# mp3-trigger.net
KiCad netlist of a schematic drawn in EAGLE
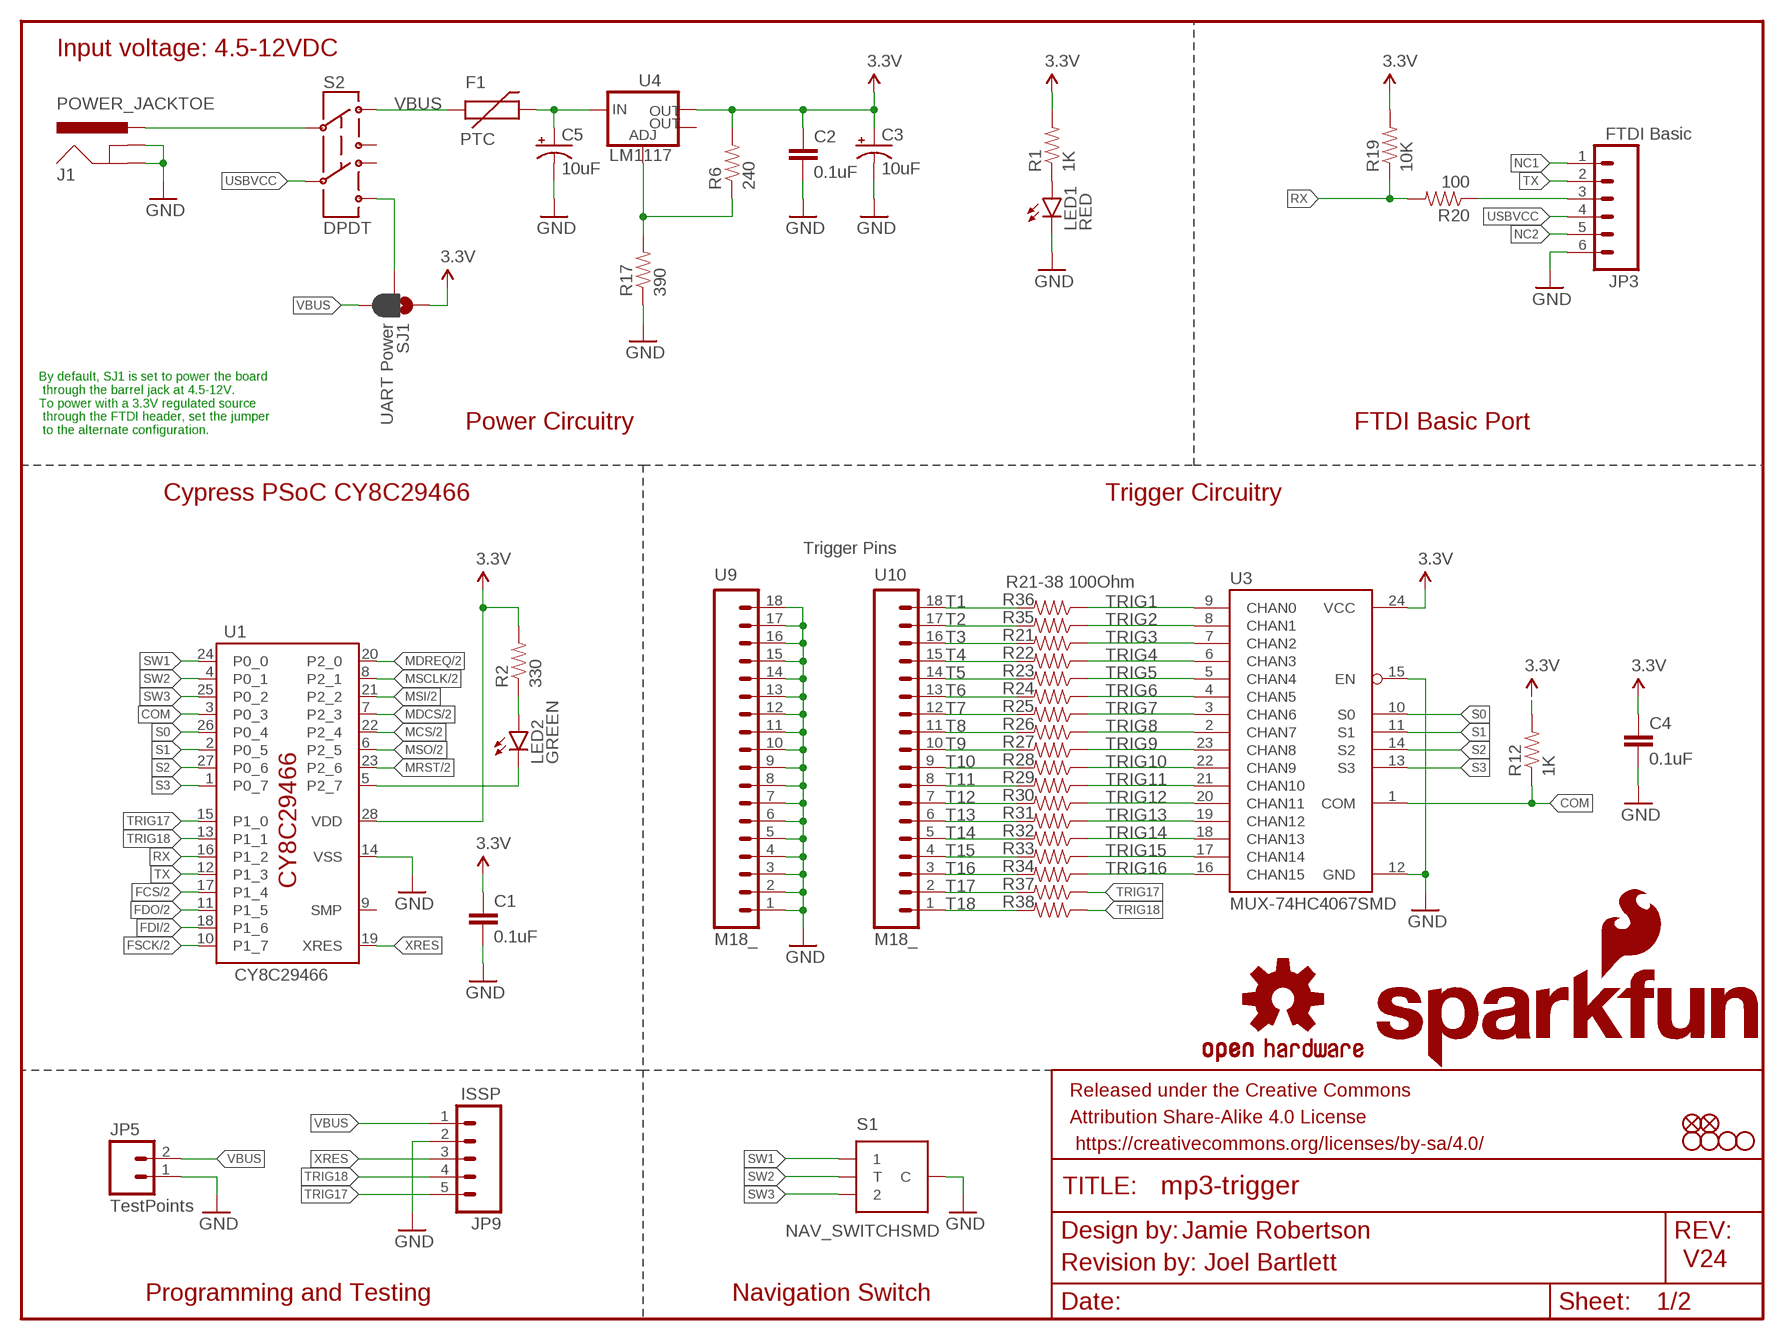
[diagram p0: schematic, sheet 1]
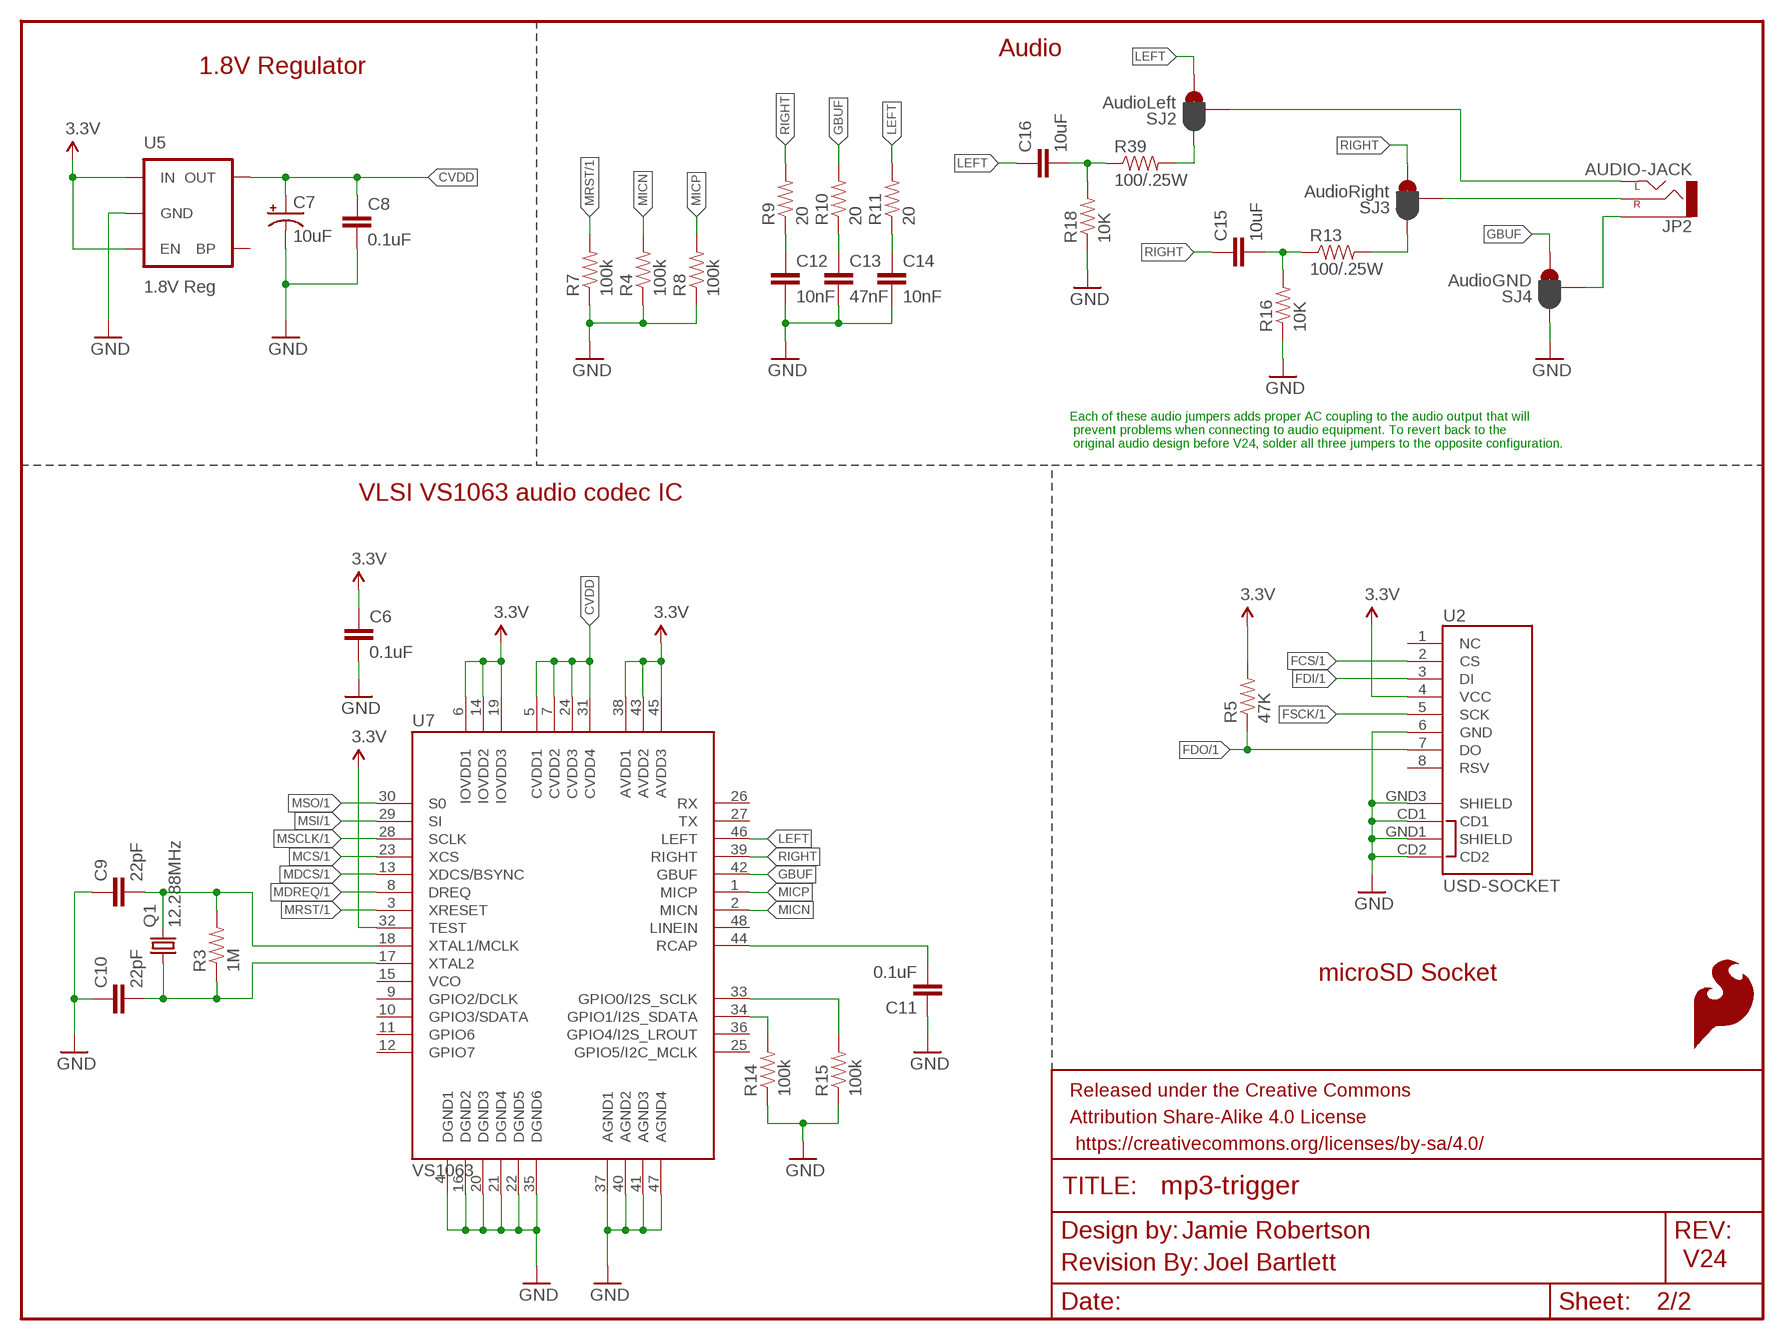
[diagram p1: schematic, sheet 2]

(export (version "E")
  (design (tool "Eeschema 10.0.6"))
  (components
    (comp (ref "C1")
      (value "0.1uF")
      (footprint "eagle-import:0603-CAP")
      (libsource (lib "eagle-import") (part "0.1UF-25V(+80/-20%)(0603)"))
    )
    (comp (ref "C2")
      (value "0.1uF")
      (footprint "eagle-import:0603-CAP")
      (libsource (lib "eagle-import") (part "0.1UF-25V(+80/-20%)(0603)"))
    )
    (comp (ref "C3")
      (value "10uF")
      (footprint "eagle-import:EIA3216")
      (libsource (lib "eagle-import") (part "10UF-16V-10%(TANT)"))
    )
    (comp (ref "C4")
      (value "0.1uF")
      (footprint "eagle-import:0603-CAP")
      (libsource (lib "eagle-import") (part "0.1UF-25V(+80/-20%)(0603)"))
    )
    (comp (ref "C5")
      (value "10uF")
      (footprint "eagle-import:EIA3216")
      (libsource (lib "eagle-import") (part "10UF-16V-10%(TANT)"))
    )
    (comp (ref "F1")
      (value "PTC")
      (footprint "eagle-import:PTC-1206")
      (libsource (lib "eagle-import") (part "PTCTHERMISTOR1206"))
    )
    (comp (ref "FRAME3")
      (value "FRAME-LETTER")
      (footprint "eagle-import:CREATIVE_COMMONS")
      (libsource (lib "eagle-import") (part "FRAME-LETTER"))
    )
    (comp (ref "J1")
      (value "POWER_JACKTOE")
      (footprint "eagle-import:POWER_JACK_SMD_OVERPASTE_TOE")
      (libsource (lib "eagle-import") (part "POWER_JACKTOE"))
    )
    (comp (ref "JP3")
      (value "FTDI Basic")
      (footprint "eagle-import:1X06")
      (libsource (lib "eagle-import") (part "M06SIP"))
    )
    (comp (ref "JP5")
      (value "TestPoints")
      (footprint "eagle-import:1X02")
      (libsource (lib "eagle-import") (part "M02PTH"))
    )
    (comp (ref "JP6")
      (value "FIDUCIAL1X2")
      (footprint "eagle-import:FIDUCIAL-1X2")
      (libsource (lib "eagle-import") (part "FIDUCIAL1X2"))
    )
    (comp (ref "JP7")
      (value "FIDUCIAL1X2")
      (footprint "eagle-import:FIDUCIAL-1X2")
      (libsource (lib "eagle-import") (part "FIDUCIAL1X2"))
    )
    (comp (ref "JP9")
      (value "ISSP")
      (footprint "eagle-import:1X05")
      (libsource (lib "eagle-import") (part "M05PTH"))
    )
    (comp (ref "LED1")
      (value "RED")
      (footprint "eagle-import:LED-1206")
      (libsource (lib "eagle-import") (part "LED-RED1206"))
    )
    (comp (ref "LED2")
      (value "GREEN")
      (footprint "eagle-import:LED-1206")
      (libsource (lib "eagle-import") (part "LED-GREEN1206"))
    )
    (comp (ref "LOGO3")
      (value "OSHW-LOGOM")
      (footprint "eagle-import:OSHW-LOGO-M")
      (libsource (lib "eagle-import") (part "OSHW-LOGOM"))
    )
    (comp (ref "R1")
      (value "1K")
      (footprint "eagle-import:0603-RES")
      (libsource (lib "eagle-import") (part "1KOHM-1/10W-1%(0603)"))
    )
    (comp (ref "R2")
      (value "330")
      (footprint "eagle-import:0603-RES")
      (libsource (lib "eagle-import") (part "330OHM1/10W1%(0603)"))
    )
    (comp (ref "R6")
      (value "240")
      (footprint "eagle-import:0603-RES")
      (libsource (lib "eagle-import") (part "240OHM1/10W1%(0603)"))
    )
    (comp (ref "R12")
      (value "1K")
      (footprint "eagle-import:0603-RES")
      (libsource (lib "eagle-import") (part "1KOHM-1/10W-1%(0603)"))
    )
    (comp (ref "R17")
      (value "390")
      (footprint "eagle-import:0603-RES")
      (libsource (lib "eagle-import") (part "390OHM1/10W1%(0603)"))
    )
    (comp (ref "R19")
      (value "10K")
      (footprint "eagle-import:0603-RES")
      (libsource (lib "eagle-import") (part "10KOHM-1/10W-1%(0603)0603"))
    )
    (comp (ref "R20")
      (value "100")
      (footprint "eagle-import:0603-RES")
      (libsource (lib "eagle-import") (part "100OHM-1/10W-1%(0603)"))
    )
    (comp (ref "R21")
      (value "100")
      (footprint "eagle-import:0603-RES")
      (libsource (lib "eagle-import") (part "100OHM-1/10W-1%(0603)"))
    )
    (comp (ref "R22")
      (value "100")
      (footprint "eagle-import:0603-RES")
      (libsource (lib "eagle-import") (part "100OHM-1/10W-1%(0603)"))
    )
    (comp (ref "R23")
      (value "100")
      (footprint "eagle-import:0603-RES")
      (libsource (lib "eagle-import") (part "100OHM-1/10W-1%(0603)"))
    )
    (comp (ref "R24")
      (value "100")
      (footprint "eagle-import:0603-RES")
      (libsource (lib "eagle-import") (part "100OHM-1/10W-1%(0603)"))
    )
    (comp (ref "R25")
      (value "100")
      (footprint "eagle-import:0603-RES")
      (libsource (lib "eagle-import") (part "100OHM-1/10W-1%(0603)"))
    )
    (comp (ref "R26")
      (value "100")
      (footprint "eagle-import:0603-RES")
      (libsource (lib "eagle-import") (part "100OHM-1/10W-1%(0603)"))
    )
    (comp (ref "R27")
      (value "100")
      (footprint "eagle-import:0603-RES")
      (libsource (lib "eagle-import") (part "100OHM-1/10W-1%(0603)"))
    )
    (comp (ref "R28")
      (value "100")
      (footprint "eagle-import:0603-RES")
      (libsource (lib "eagle-import") (part "100OHM-1/10W-1%(0603)"))
    )
    (comp (ref "R29")
      (value "100")
      (footprint "eagle-import:0603-RES")
      (libsource (lib "eagle-import") (part "100OHM-1/10W-1%(0603)"))
    )
    (comp (ref "R30")
      (value "100")
      (footprint "eagle-import:0603-RES")
      (libsource (lib "eagle-import") (part "100OHM-1/10W-1%(0603)"))
    )
    (comp (ref "R31")
      (value "100")
      (footprint "eagle-import:0603-RES")
      (libsource (lib "eagle-import") (part "100OHM-1/10W-1%(0603)"))
    )
    (comp (ref "R32")
      (value "100")
      (footprint "eagle-import:0603-RES")
      (libsource (lib "eagle-import") (part "100OHM-1/10W-1%(0603)"))
    )
    (comp (ref "R33")
      (value "100")
      (footprint "eagle-import:0603-RES")
      (libsource (lib "eagle-import") (part "100OHM-1/10W-1%(0603)"))
    )
    (comp (ref "R34")
      (value "100")
      (footprint "eagle-import:0603-RES")
      (libsource (lib "eagle-import") (part "100OHM-1/10W-1%(0603)"))
    )
    (comp (ref "R35")
      (value "100")
      (footprint "eagle-import:0603-RES")
      (libsource (lib "eagle-import") (part "100OHM-1/10W-1%(0603)"))
    )
    (comp (ref "R36")
      (value "100")
      (footprint "eagle-import:0603-RES")
      (libsource (lib "eagle-import") (part "100OHM-1/10W-1%(0603)"))
    )
    (comp (ref "R37")
      (value "100")
      (footprint "eagle-import:0603-RES")
      (libsource (lib "eagle-import") (part "100OHM-1/10W-1%(0603)"))
    )
    (comp (ref "R38")
      (value "100")
      (footprint "eagle-import:0603-RES")
      (libsource (lib "eagle-import") (part "100OHM-1/10W-1%(0603)"))
    )
    (comp (ref "S1")
      (value "NAV_SWITCHSMD")
      (footprint "eagle-import:NAV_SWITCH")
      (libsource (lib "eagle-import") (part "NAV_SWITCHSMD"))
    )
    (comp (ref "S2")
      (value "DPDT")
      (footprint "eagle-import:AYZ0202")
      (libsource (lib "eagle-import") (part "SWITCH-DPDTAYZ0202"))
    )
    (comp (ref "SJ1")
      (value "UART Power")
      (footprint "eagle-import:PAD-JUMPER-3-2OF3_NC_BY_PASTE_YES_SILK_FULL_BOX")
      (libsource (lib "eagle-import") (part "JUMPER-PAD-3-2OF3_NC_BY_PASTE"))
    )
    (comp (ref "U$1")
      (value "SFE_LOGO_NAME_FLAME.2_INCH")
      (footprint "eagle-import:SFE_LOGO_NAME_FLAME_.2")
      (libsource (lib "eagle-import") (part "SFE_LOGO_NAME_FLAME.2_INCH"))
    )
    (comp (ref "U$12")
      (value "STAND-OFF")
      (footprint "eagle-import:STAND-OFF")
      (libsource (lib "eagle-import") (part "STAND-OFF"))
    )
    (comp (ref "U$13")
      (value "STAND-OFF")
      (footprint "eagle-import:STAND-OFF")
      (libsource (lib "eagle-import") (part "STAND-OFF"))
    )
    (comp (ref "U$14")
      (value "STAND-OFF")
      (footprint "eagle-import:STAND-OFF")
      (libsource (lib "eagle-import") (part "STAND-OFF"))
    )
    (comp (ref "U$15")
      (value "STAND-OFF")
      (footprint "eagle-import:STAND-OFF")
      (libsource (lib "eagle-import") (part "STAND-OFF"))
    )
    (comp (ref "U1")
      (value "CY8C29466")
      (footprint "eagle-import:SOIC-28")
      (libsource (lib "eagle-import") (part "CY8C29466-24"))
    )
    (comp (ref "U3")
      (value "MUX-74HC4067SMD")
      (footprint "eagle-import:SSOP24")
      (libsource (lib "eagle-import") (part "MUX-74HC4067SMD"))
    )
    (comp (ref "U4")
      (value "LM1117")
      (footprint "eagle-import:SOT223")
      (libsource (lib "eagle-import") (part "V_REG_LM1117SOT223"))
    )
    (comp (ref "U9")
      (value "M18_")
      (footprint "eagle-import:1X18")
      (libsource (lib "eagle-import") (part "M18_"))
    )
    (comp (ref "U10")
      (value "M18_")
      (footprint "eagle-import:1X18")
      (libsource (lib "eagle-import") (part "M18_"))
    )
    (comp (ref "C6")
      (value "0.1uF")
      (footprint "eagle-import:0603-CAP")
      (libsource (lib "eagle-import") (part "0.1UF-25V(+80/-20%)(0603)"))
    )
    (comp (ref "C7")
      (value "10uF")
      (footprint "eagle-import:EIA3216")
      (libsource (lib "eagle-import") (part "10UF-16V-10%(TANT)"))
    )
    (comp (ref "C8")
      (value "0.1uF")
      (footprint "eagle-import:0603-CAP")
      (libsource (lib "eagle-import") (part "0.1UF-25V(+80/-20%)(0603)"))
    )
    (comp (ref "C9")
      (value "22pF")
      (footprint "eagle-import:0603-CAP")
      (libsource (lib "eagle-import") (part "22PF-50V-5%(0603)"))
    )
    (comp (ref "C10")
      (value "22pF")
      (footprint "eagle-import:0603-CAP")
      (libsource (lib "eagle-import") (part "22PF-50V-5%(0603)"))
    )
    (comp (ref "C11")
      (value "0.1uF")
      (footprint "eagle-import:0603-CAP")
      (libsource (lib "eagle-import") (part "0.1UF-25V(+80/-20%)(0603)"))
    )
    (comp (ref "C12")
      (value "10nF")
      (footprint "eagle-import:0603-CAP")
      (libsource (lib "eagle-import") (part "10NF/10000PF-50V-10%(0603)"))
    )
    (comp (ref "C13")
      (value "47nF")
      (footprint "eagle-import:0603-CAP")
      (libsource (lib "eagle-import") (part "47NF(0.047UF/47000PF)-25V-5%(0603)SMD"))
    )
    (comp (ref "C14")
      (value "10nF")
      (footprint "eagle-import:0603-CAP")
      (libsource (lib "eagle-import") (part "10NF/10000PF-50V-10%(0603)"))
    )
    (comp (ref "C15")
      (value "10uF")
      (footprint "eagle-import:0603-CAP")
      (libsource (lib "eagle-import") (part "10UF-6.3V-20%(0603)"))
    )
    (comp (ref "C16")
      (value "10uF")
      (footprint "eagle-import:0603-CAP")
      (libsource (lib "eagle-import") (part "10UF-6.3V-20%(0603)"))
    )
    (comp (ref "FRAME1")
      (value "FRAME-LETTERNO_PACKAGE")
      (footprint "eagle-import:DUMMY")
      (fields (field (name "DESIGNER") "Nobody"))
      (libsource (lib "eagle-import") (part "FRAME-LETTERNO_PACKAGE"))
    )
    (comp (ref "JP2")
      (value "AUDIO-JACK")
      (footprint "eagle-import:AUDIO-JACK-3.5MM-SMD")
      (libsource (lib "eagle-import") (part "AUDIO-JACKSMD2"))
    )
    (comp (ref "LOGO1")
      (value "SFE_LOGO_FLAME.3_INCH")
      (footprint "eagle-import:SFE_LOGO_FLAME_.3")
      (libsource (lib "eagle-import") (part "SFE_LOGO_FLAME.3_INCH"))
    )
    (comp (ref "Q1")
      (value "12.288MHz")
      (footprint "eagle-import:CRYSTAL-SMD-5X3")
      (libsource (lib "eagle-import") (part "CRYSTALCRYSTAL-SMD-5X3-12.288MHZ"))
    )
    (comp (ref "R3")
      (value "1M")
      (footprint "eagle-import:0603-RES")
      (libsource (lib "eagle-import") (part "1MOHM-1/10W-1%(0603)"))
    )
    (comp (ref "R4")
      (value "100k")
      (footprint "eagle-import:0603-RES")
      (libsource (lib "eagle-import") (part "100KOHM-1/10W-1%(0603)"))
    )
    (comp (ref "R5")
      (value "47K")
      (footprint "eagle-import:0603-RES")
      (libsource (lib "eagle-import") (part "47KOHM1/10W1%(0603)"))
    )
    (comp (ref "R7")
      (value "100k")
      (footprint "eagle-import:0603-RES")
      (libsource (lib "eagle-import") (part "100KOHM-1/10W-1%(0603)"))
    )
    (comp (ref "R8")
      (value "100k")
      (footprint "eagle-import:0603-RES")
      (libsource (lib "eagle-import") (part "100KOHM-1/10W-1%(0603)"))
    )
    (comp (ref "R9")
      (value "20")
      (footprint "eagle-import:0603-RES")
      (libsource (lib "eagle-import") (part "20OHM1/10W1%(0603)SMD"))
    )
    (comp (ref "R10")
      (value "20")
      (footprint "eagle-import:0603-RES")
      (libsource (lib "eagle-import") (part "20OHM1/10W1%(0603)SMD"))
    )
    (comp (ref "R11")
      (value "20")
      (footprint "eagle-import:0603-RES")
      (libsource (lib "eagle-import") (part "20OHM1/10W1%(0603)SMD"))
    )
    (comp (ref "R13")
      (value "100/.25W")
      (footprint "eagle-import:0603-RES")
      (libsource (lib "eagle-import") (part "100OHM-1/4W-5%(0603)"))
    )
    (comp (ref "R14")
      (value "100k")
      (footprint "eagle-import:0603-RES")
      (libsource (lib "eagle-import") (part "100KOHM-1/10W-1%(0603)"))
    )
    (comp (ref "R15")
      (value "100k")
      (footprint "eagle-import:0603-RES")
      (libsource (lib "eagle-import") (part "100KOHM-1/10W-1%(0603)"))
    )
    (comp (ref "R16")
      (value "10K")
      (footprint "eagle-import:0603-RES")
      (libsource (lib "eagle-import") (part "10KOHM-1/10W-1%(0603)0603"))
    )
    (comp (ref "R18")
      (value "10K")
      (footprint "eagle-import:0603-RES")
      (libsource (lib "eagle-import") (part "10KOHM-1/10W-1%(0603)0603"))
    )
    (comp (ref "R39")
      (value "100/.25W")
      (footprint "eagle-import:0603-RES")
      (libsource (lib "eagle-import") (part "100OHM-1/4W-5%(0603)"))
    )
    (comp (ref "SJ2")
      (value "AudioLeft")
      (footprint "eagle-import:PAD-HUMPER-3-1&2_NC_BY_PASTE_YES_SILK_FULL_BOX")
      (libsource (lib "eagle-import") (part "JUMPER_PAD-3-1&2_NC_BY_PASTE"))
    )
    (comp (ref "SJ3")
      (value "AudioRight")
      (footprint "eagle-import:PAD-HUMPER-3-1&2_NC_BY_PASTE_YES_SILK_FULL_BOX")
      (libsource (lib "eagle-import") (part "JUMPER_PAD-3-1&2_NC_BY_PASTE"))
    )
    (comp (ref "SJ4")
      (value "AudioGND")
      (footprint "eagle-import:PAD-HUMPER-3-1&2_NC_BY_PASTE_YES_SILK_FULL_BOX")
      (libsource (lib "eagle-import") (part "JUMPER_PAD-3-1&2_NC_BY_PASTE"))
    )
    (comp (ref "U$4")
      (value "REVISION")
      (footprint "eagle-import:REVISION")
      (libsource (lib "eagle-import") (part "REVISION"))
    )
    (comp (ref "U2")
      (value "USD-SOCKET")
      (footprint "eagle-import:MICROSD_1_1")
      (libsource (lib "eagle-import") (part "USD-SOCKET"))
    )
    (comp (ref "U5")
      (value "1.8V Reg")
      (footprint "eagle-import:SC70")
      (libsource (lib "eagle-import") (part "V_REG_LDOSMD2"))
    )
    (comp (ref "U7")
      (value "VS1063")
      (footprint "eagle-import:LQFP-48")
      (libsource (lib "eagle-import") (part "VS1063SMD"))
    )
  )
  (nets
    (net (code "1") (name "3.3V") (class "Default")
      (node (ref "C1") (pin "1") (pinfunction "1_1") (pintype "passive"))
      (node (ref "C2") (pin "1") (pinfunction "1_1") (pintype "passive"))
      (node (ref "C3") (pin "A") (pinfunction "+_A") (pintype "passive"))
      (node (ref "C4") (pin "1") (pinfunction "1_1") (pintype "passive"))
      (node (ref "C6") (pin "1") (pinfunction "1_1") (pintype "passive"))
      (node (ref "R1") (pin "2") (pinfunction "2_2") (pintype "passive"))
      (node (ref "R12") (pin "2") (pinfunction "2_2") (pintype "passive"))
      (node (ref "R19") (pin "2") (pinfunction "2_2") (pintype "passive"))
      (node (ref "R2") (pin "2") (pinfunction "2_2") (pintype "passive"))
      (node (ref "R5") (pin "2") (pinfunction "2_2") (pintype "passive"))
      (node (ref "R6") (pin "2") (pinfunction "2_2") (pintype "passive"))
      (node (ref "SJ1") (pin "1") (pinfunction "1_1") (pintype "passive"))
      (node (ref "U1") (pin "28") (pinfunction "VDD_28") (pintype "power_in"))
      (node (ref "U2") (pin "4") (pinfunction "VCC_4") (pintype "bidirectional"))
      (node (ref "U3") (pin "24") (pinfunction "VCC_24") (pintype "bidirectional"))
      (node (ref "U4") (pin "2") (pinfunction "OUT_2") (pintype "output"))
      (node (ref "U5") (pin "1") (pinfunction "IN_1") (pintype "input"))
      (node (ref "U5") (pin "3") (pinfunction "EN_3") (pintype "input"))
      (node (ref "U7") (pin "14") (pinfunction "IOVDD2_14") (pintype "bidirectional"))
      (node (ref "U7") (pin "19") (pinfunction "IOVDD3_19") (pintype "bidirectional"))
      (node (ref "U7") (pin "32") (pinfunction "TEST_32") (pintype "bidirectional"))
      (node (ref "U7") (pin "38") (pinfunction "AVDD1_38") (pintype "bidirectional"))
      (node (ref "U7") (pin "43") (pinfunction "AVDD2_43") (pintype "bidirectional"))
      (node (ref "U7") (pin "45") (pinfunction "AVDD3_45") (pintype "bidirectional"))
      (node (ref "U7") (pin "6") (pinfunction "IOVDD1_6") (pintype "bidirectional"))
    )
    (net (code "2") (name "COM") (class "Default")
      (node (ref "R12") (pin "1") (pinfunction "1_1") (pintype "passive"))
      (node (ref "U1") (pin "3") (pinfunction "P0_3_3") (pintype "bidirectional"))
      (node (ref "U3") (pin "1") (pinfunction "COM_1") (pintype "bidirectional"))
    )
    (net (code "3") (name "CVDD") (class "Default")
      (node (ref "C7") (pin "A") (pinfunction "+_A") (pintype "passive"))
      (node (ref "C8") (pin "1") (pinfunction "1_1") (pintype "passive"))
      (node (ref "U5") (pin "5") (pinfunction "OUT_5") (pintype "passive"))
      (node (ref "U7") (pin "24") (pinfunction "CVDD3_24") (pintype "bidirectional"))
      (node (ref "U7") (pin "31") (pinfunction "CVDD4_31") (pintype "bidirectional"))
      (node (ref "U7") (pin "5") (pinfunction "CVDD1_5") (pintype "bidirectional"))
      (node (ref "U7") (pin "7") (pinfunction "CVDD2_7") (pintype "bidirectional"))
    )
    (net (code "4") (name "FCS") (class "Default")
      (node (ref "U1") (pin "17") (pinfunction "P1_4_17") (pintype "bidirectional"))
      (node (ref "U2") (pin "2") (pinfunction "CS_2") (pintype "bidirectional"))
    )
    (net (code "5") (name "FDI") (class "Default")
      (node (ref "U1") (pin "18") (pinfunction "P1_6_18") (pintype "bidirectional"))
      (node (ref "U2") (pin "3") (pinfunction "DI_3") (pintype "bidirectional"))
    )
    (net (code "6") (name "FDO") (class "Default")
      (node (ref "R5") (pin "1") (pinfunction "1_1") (pintype "passive"))
      (node (ref "U1") (pin "11") (pinfunction "P1_5_11") (pintype "bidirectional"))
      (node (ref "U2") (pin "7") (pinfunction "DO_7") (pintype "bidirectional"))
    )
    (net (code "7") (name "FSCK") (class "Default")
      (node (ref "U1") (pin "10") (pinfunction "P1_7_10") (pintype "bidirectional"))
      (node (ref "U2") (pin "5") (pinfunction "SCK_5") (pintype "bidirectional"))
    )
    (net (code "8") (name "GBUF") (class "Default")
      (node (ref "R10") (pin "2") (pinfunction "2_2") (pintype "passive"))
      (node (ref "SJ4") (pin "3") (pinfunction "3_3") (pintype "passive"))
      (node (ref "U7") (pin "42") (pinfunction "GBUF_42") (pintype "bidirectional"))
    )
    (net (code "9") (name "GND") (class "Default")
      (node (ref "C1") (pin "2") (pinfunction "2_2") (pintype "passive"))
      (node (ref "C10") (pin "1") (pinfunction "1_1") (pintype "passive"))
      (node (ref "C11") (pin "1") (pinfunction "1_1") (pintype "passive"))
      (node (ref "C12") (pin "2") (pinfunction "2_2") (pintype "passive"))
      (node (ref "C13") (pin "2") (pinfunction "2_2") (pintype "passive"))
      (node (ref "C14") (pin "2") (pinfunction "2_2") (pintype "passive"))
      (node (ref "C2") (pin "2") (pinfunction "2_2") (pintype "passive"))
      (node (ref "C3") (pin "C") (pinfunction "-_C") (pintype "passive"))
      (node (ref "C4") (pin "2") (pinfunction "2_2") (pintype "passive"))
      (node (ref "C5") (pin "C") (pinfunction "-_C") (pintype "passive"))
      (node (ref "C6") (pin "2") (pinfunction "2_2") (pintype "passive"))
      (node (ref "C7") (pin "C") (pinfunction "-_C") (pintype "passive"))
      (node (ref "C8") (pin "2") (pinfunction "2_2") (pintype "passive"))
      (node (ref "C9") (pin "1") (pinfunction "1_1") (pintype "passive"))
      (node (ref "J1") (pin "GND") (pinfunction "GNDBREAK_GND") (pintype "bidirectional"))
      (node (ref "J1") (pin "P$4") (pinfunction "GND_P$4") (pintype "bidirectional"))
      (node (ref "JP3") (pin "6") (pinfunction "6_6") (pintype "passive"))
      (node (ref "JP5") (pin "1") (pinfunction "1_1") (pintype "passive"))
      (node (ref "JP9") (pin "2") (pinfunction "2_2") (pintype "passive"))
      (node (ref "LED1") (pin "C") (pinfunction "C_C") (pintype "passive"))
      (node (ref "R14") (pin "1") (pinfunction "1_1") (pintype "passive"))
      (node (ref "R15") (pin "1") (pinfunction "1_1") (pintype "passive"))
      (node (ref "R16") (pin "1") (pinfunction "1_1") (pintype "passive"))
      (node (ref "R17") (pin "1") (pinfunction "1_1") (pintype "passive"))
      (node (ref "R18") (pin "1") (pinfunction "1_1") (pintype "passive"))
      (node (ref "R4") (pin "1") (pinfunction "1_1") (pintype "passive"))
      (node (ref "R7") (pin "1") (pinfunction "1_1") (pintype "passive"))
      (node (ref "R8") (pin "1") (pinfunction "1_1") (pintype "passive"))
      (node (ref "S1") (pin "C") (pinfunction "C_C") (pintype "power_in"))
      (node (ref "SJ4") (pin "1") (pinfunction "1_1") (pintype "passive"))
      (node (ref "U1") (pin "14") (pinfunction "VSS_14") (pintype "power_in"))
      (node (ref "U2") (pin "6") (pinfunction "GND_6") (pintype "bidirectional"))
      (node (ref "U2") (pin "CD1") (pinfunction "CD1_CD1") (pintype "bidirectional"))
      (node (ref "U2") (pin "CD2") (pinfunction "CD2_CD2") (pintype "bidirectional"))
      (node (ref "U2") (pin "GND1") (pinfunction "SHIELD_GND1") (pintype "bidirectional"))
      (node (ref "U2") (pin "GND3") (pinfunction "SHIELD_GND3") (pintype "bidirectional"))
      (node (ref "U3") (pin "12") (pinfunction "GND_12") (pintype "bidirectional"))
      (node (ref "U3") (pin "15") (pinfunction "EN_15") (pintype "input"))
      (node (ref "U5") (pin "2") (pinfunction "GND_2") (pintype "input"))
      (node (ref "U7") (pin "16") (pinfunction "DGND2_16") (pintype "bidirectional"))
      (node (ref "U7") (pin "20") (pinfunction "DGND3_20") (pintype "bidirectional"))
      (node (ref "U7") (pin "21") (pinfunction "DGND4_21") (pintype "bidirectional"))
      (node (ref "U7") (pin "22") (pinfunction "DGND5_22") (pintype "bidirectional"))
      (node (ref "U7") (pin "35") (pinfunction "DGND6_35") (pintype "bidirectional"))
      (node (ref "U7") (pin "37") (pinfunction "AGND1_37") (pintype "bidirectional"))
      (node (ref "U7") (pin "4") (pinfunction "DGND1_4") (pintype "bidirectional"))
      (node (ref "U7") (pin "40") (pinfunction "AGND2_40") (pintype "bidirectional"))
      (node (ref "U7") (pin "41") (pinfunction "AGND3_41") (pintype "bidirectional"))
      (node (ref "U7") (pin "47") (pinfunction "AGND4_47") (pintype "bidirectional"))
      (node (ref "U9") (pin "1") (pinfunction "1_1") (pintype "passive"))
      (node (ref "U9") (pin "10") (pinfunction "10_10") (pintype "passive"))
      (node (ref "U9") (pin "11") (pinfunction "11_11") (pintype "passive"))
      (node (ref "U9") (pin "12") (pinfunction "12_12") (pintype "passive"))
      (node (ref "U9") (pin "13") (pinfunction "13_13") (pintype "passive"))
      (node (ref "U9") (pin "14") (pinfunction "14_14") (pintype "passive"))
      (node (ref "U9") (pin "15") (pinfunction "15_15") (pintype "passive"))
      (node (ref "U9") (pin "16") (pinfunction "16_16") (pintype "passive"))
      (node (ref "U9") (pin "17") (pinfunction "17_17") (pintype "passive"))
      (node (ref "U9") (pin "18") (pinfunction "18_18") (pintype "passive"))
      (node (ref "U9") (pin "2") (pinfunction "2_2") (pintype "passive"))
      (node (ref "U9") (pin "3") (pinfunction "3_3") (pintype "passive"))
      (node (ref "U9") (pin "4") (pinfunction "4_4") (pintype "passive"))
      (node (ref "U9") (pin "5") (pinfunction "5_5") (pintype "passive"))
      (node (ref "U9") (pin "6") (pinfunction "6_6") (pintype "passive"))
      (node (ref "U9") (pin "7") (pinfunction "7_7") (pintype "passive"))
      (node (ref "U9") (pin "8") (pinfunction "8_8") (pintype "passive"))
      (node (ref "U9") (pin "9") (pinfunction "9_9") (pintype "passive"))
    )
    (net (code "10") (name "LEFT") (class "Default")
      (node (ref "C16") (pin "1") (pinfunction "1_1") (pintype "passive"))
      (node (ref "R11") (pin "2") (pinfunction "2_2") (pintype "passive"))
      (node (ref "SJ2") (pin "3") (pinfunction "3_3") (pintype "passive"))
      (node (ref "U7") (pin "46") (pinfunction "LEFT_46") (pintype "bidirectional"))
    )
    (net (code "11") (name "MCS") (class "Default")
      (node (ref "U1") (pin "22") (pinfunction "P2_4_22") (pintype "bidirectional"))
      (node (ref "U7") (pin "23") (pinfunction "XCS_23") (pintype "bidirectional"))
    )
    (net (code "12") (name "MDCS") (class "Default")
      (node (ref "U1") (pin "7") (pinfunction "P2_3_7") (pintype "bidirectional"))
      (node (ref "U7") (pin "13") (pinfunction "XDCS/BSYNC_13") (pintype "bidirectional"))
    )
    (net (code "13") (name "MDREQ") (class "Default")
      (node (ref "U1") (pin "20") (pinfunction "P2_0_20") (pintype "bidirectional"))
      (node (ref "U7") (pin "8") (pinfunction "DREQ_8") (pintype "bidirectional"))
    )
    (net (code "14") (name "MICN") (class "Default")
      (node (ref "R4") (pin "2") (pinfunction "2_2") (pintype "passive"))
      (node (ref "U7") (pin "2") (pinfunction "MICN_2") (pintype "bidirectional"))
    )
    (net (code "15") (name "MICP") (class "Default")
      (node (ref "R8") (pin "2") (pinfunction "2_2") (pintype "passive"))
      (node (ref "U7") (pin "1") (pinfunction "MICP_1") (pintype "bidirectional"))
    )
    (net (code "16") (name "MRST") (class "Default")
      (node (ref "R7") (pin "2") (pinfunction "2_2") (pintype "passive"))
      (node (ref "U1") (pin "23") (pinfunction "P2_6_23") (pintype "bidirectional"))
      (node (ref "U7") (pin "3") (pinfunction "XRESET_3") (pintype "bidirectional"))
    )
    (net (code "17") (name "MSCLK") (class "Default")
      (node (ref "U1") (pin "8") (pinfunction "P2_1_8") (pintype "bidirectional"))
      (node (ref "U7") (pin "28") (pinfunction "SCLK_28") (pintype "bidirectional"))
    )
    (net (code "18") (name "MSI") (class "Default")
      (node (ref "U1") (pin "21") (pinfunction "P2_2_21") (pintype "bidirectional"))
      (node (ref "U7") (pin "29") (pinfunction "SI_29") (pintype "bidirectional"))
    )
    (net (code "19") (name "MSO") (class "Default")
      (node (ref "U1") (pin "6") (pinfunction "P2_5_6") (pintype "bidirectional"))
      (node (ref "U7") (pin "30") (pinfunction "S0_30") (pintype "bidirectional"))
    )
    (net (code "20") (name "NC1") (class "Default")
      (node (ref "JP3") (pin "1") (pinfunction "1_1") (pintype "passive"))
    )
    (net (code "21") (name "NC2") (class "Default")
      (node (ref "JP3") (pin "5") (pinfunction "5_5") (pintype "passive"))
    )
    (net (code "22") (name "Net-(C5-+)") (class "Default")
      (node (ref "C5") (pin "A") (pinfunction "+_A") (pintype "passive"))
      (node (ref "F1") (pin "2") (pinfunction "2_2") (pintype "bidirectional"))
      (node (ref "U4") (pin "3") (pinfunction "IN_3") (pintype "input"))
    )
    (net (code "23") (name "Net-(C12-Pad1)") (class "Default")
      (node (ref "C12") (pin "1") (pinfunction "1_1") (pintype "passive"))
      (node (ref "R9") (pin "1") (pinfunction "1_1") (pintype "passive"))
    )
    (net (code "24") (name "Net-(C13-Pad1)") (class "Default")
      (node (ref "C13") (pin "1") (pinfunction "1_1") (pintype "passive"))
      (node (ref "R10") (pin "1") (pinfunction "1_1") (pintype "passive"))
    )
    (net (code "25") (name "Net-(C14-Pad1)") (class "Default")
      (node (ref "C14") (pin "1") (pinfunction "1_1") (pintype "passive"))
      (node (ref "R11") (pin "1") (pinfunction "1_1") (pintype "passive"))
    )
    (net (code "26") (name "Net-(C15-Pad2)") (class "Default")
      (node (ref "C15") (pin "2") (pinfunction "2_2") (pintype "passive"))
      (node (ref "R13") (pin "1") (pinfunction "1_1") (pintype "passive"))
      (node (ref "R16") (pin "2") (pinfunction "2_2") (pintype "passive"))
    )
    (net (code "27") (name "Net-(C16-Pad2)") (class "Default")
      (node (ref "C16") (pin "2") (pinfunction "2_2") (pintype "passive"))
      (node (ref "R18") (pin "2") (pinfunction "2_2") (pintype "passive"))
      (node (ref "R39") (pin "1") (pinfunction "1_1") (pintype "passive"))
    )
    (net (code "28") (name "Net-(J1-PWR)") (class "Default")
      (node (ref "J1") (pin "VIN0") (pinfunction "PWR_VIN0") (pintype "bidirectional"))
      (node (ref "S2") (pin "2") (pinfunction "2_2") (pintype "bidirectional"))
    )
    (net (code "29") (name "Net-(JP2-LEFT)") (class "Default")
      (node (ref "JP2") (pin "TIP") (pinfunction "LEFT_TIP") (pintype "bidirectional"))
      (node (ref "SJ2") (pin "2") (pinfunction "2_2") (pintype "passive"))
    )
    (net (code "30") (name "Net-(JP2-PadSLEEVE)") (class "Default")
      (node (ref "JP2") (pin "SLEEVE") (pinfunction "SLEEVE_SLEEVE") (pintype "bidirectional"))
      (node (ref "SJ4") (pin "2") (pinfunction "2_2") (pintype "passive"))
    )
    (net (code "31") (name "Net-(JP2-RIGHT)") (class "Default")
      (node (ref "JP2") (pin "RING") (pinfunction "RIGHT_RING") (pintype "bidirectional"))
      (node (ref "SJ3") (pin "2") (pinfunction "2_2") (pintype "passive"))
    )
    (net (code "32") (name "Net-(JP3-Pad3)") (class "Default")
      (node (ref "JP3") (pin "3") (pinfunction "3_3") (pintype "passive"))
      (node (ref "R20") (pin "1") (pinfunction "1_1") (pintype "passive"))
    )
    (net (code "33") (name "Net-(LED1-PadA)") (class "Default")
      (node (ref "LED1") (pin "A") (pinfunction "A_A") (pintype "passive"))
      (node (ref "R1") (pin "1") (pinfunction "1_1") (pintype "passive"))
    )
    (net (code "34") (name "Net-(LED2-PadA)") (class "Default")
      (node (ref "LED2") (pin "A") (pinfunction "A_A") (pintype "passive"))
      (node (ref "R2") (pin "1") (pinfunction "1_1") (pintype "passive"))
    )
    (net (code "35") (name "Net-(Q1-2)") (class "Default")
      (node (ref "C9") (pin "2") (pinfunction "2_2") (pintype "passive"))
      (node (ref "Q1") (pin "3") (pinfunction "2_3") (pintype "passive"))
      (node (ref "R3") (pin "2") (pinfunction "2_2") (pintype "passive"))
      (node (ref "U7") (pin "18") (pinfunction "XTAL1/MCLK_18") (pintype "bidirectional"))
    )
    (net (code "36") (name "Net-(R13-Pad2)") (class "Default")
      (node (ref "R13") (pin "2") (pinfunction "2_2") (pintype "passive"))
      (node (ref "SJ3") (pin "1") (pinfunction "1_1") (pintype "passive"))
    )
    (net (code "37") (name "Net-(R39-Pad2)") (class "Default")
      (node (ref "R39") (pin "2") (pinfunction "2_2") (pintype "passive"))
      (node (ref "SJ2") (pin "1") (pinfunction "1_1") (pintype "passive"))
    )
    (net (code "38") (name "Net-(S2-Pad6)") (class "Default")
      (node (ref "S2") (pin "6") (pinfunction "6_6") (pintype "bidirectional"))
      (node (ref "SJ1") (pin "2") (pinfunction "2_2") (pintype "passive"))
    )
    (net (code "39") (name "Net-(U1-P2_7)") (class "Default")
      (node (ref "LED2") (pin "C") (pinfunction "C_C") (pintype "passive"))
      (node (ref "U1") (pin "5") (pinfunction "P2_7_5") (pintype "bidirectional"))
    )
    (net (code "40") (name "Net-(U4-ADJ)") (class "Default")
      (node (ref "R17") (pin "2") (pinfunction "2_2") (pintype "passive"))
      (node (ref "R6") (pin "1") (pinfunction "1_1") (pintype "passive"))
      (node (ref "U4") (pin "1") (pinfunction "ADJ_1") (pintype "input"))
    )
    (net (code "41") (name "Net-(U7-GPIO0{slash}I2S_SCLK)") (class "Default")
      (node (ref "R15") (pin "2") (pinfunction "2_2") (pintype "passive"))
      (node (ref "U7") (pin "33") (pinfunction "GPIO0/I2S_SCLK_33") (pintype "bidirectional"))
    )
    (net (code "42") (name "Net-(U7-GPIO1{slash}I2S_SDATA)") (class "Default")
      (node (ref "R14") (pin "2") (pinfunction "2_2") (pintype "passive"))
      (node (ref "U7") (pin "34") (pinfunction "GPIO1/I2S_SDATA_34") (pintype "bidirectional"))
    )
    (net (code "43") (name "Net-(U7-RCAP)") (class "Default")
      (node (ref "C11") (pin "2") (pinfunction "2_2") (pintype "passive"))
      (node (ref "U7") (pin "44") (pinfunction "RCAP_44") (pintype "bidirectional"))
    )
    (net (code "44") (name "Net-(U7-XTAL2)") (class "Default")
      (node (ref "C10") (pin "2") (pinfunction "2_2") (pintype "passive"))
      (node (ref "Q1") (pin "1") (pinfunction "1_1") (pintype "passive"))
      (node (ref "R3") (pin "1") (pinfunction "1_1") (pintype "passive"))
      (node (ref "U7") (pin "17") (pinfunction "XTAL2_17") (pintype "bidirectional"))
    )
    (net (code "45") (name "RIGHT") (class "Default")
      (node (ref "C15") (pin "1") (pinfunction "1_1") (pintype "passive"))
      (node (ref "R9") (pin "2") (pinfunction "2_2") (pintype "passive"))
      (node (ref "SJ3") (pin "3") (pinfunction "3_3") (pintype "passive"))
      (node (ref "U7") (pin "39") (pinfunction "RIGHT_39") (pintype "bidirectional"))
    )
    (net (code "46") (name "RX") (class "Default")
      (node (ref "R19") (pin "1") (pinfunction "1_1") (pintype "passive"))
      (node (ref "R20") (pin "2") (pinfunction "2_2") (pintype "passive"))
      (node (ref "U1") (pin "16") (pinfunction "P1_2_16") (pintype "bidirectional"))
    )
    (net (code "47") (name "S0") (class "Default")
      (node (ref "U1") (pin "26") (pinfunction "P0_4_26") (pintype "bidirectional"))
      (node (ref "U3") (pin "10") (pinfunction "S0_10") (pintype "input"))
    )
    (net (code "48") (name "S1") (class "Default")
      (node (ref "U1") (pin "2") (pinfunction "P0_5_2") (pintype "bidirectional"))
      (node (ref "U3") (pin "11") (pinfunction "S1_11") (pintype "input"))
    )
    (net (code "49") (name "S2") (class "Default")
      (node (ref "U1") (pin "27") (pinfunction "P0_6_27") (pintype "bidirectional"))
      (node (ref "U3") (pin "14") (pinfunction "S2_14") (pintype "input"))
    )
    (net (code "50") (name "S3") (class "Default")
      (node (ref "U1") (pin "1") (pinfunction "P0_7_1") (pintype "bidirectional"))
      (node (ref "U3") (pin "13") (pinfunction "S3_13") (pintype "input"))
    )
    (net (code "51") (name "SW1") (class "Default")
      (node (ref "S1") (pin "1") (pinfunction "1_1") (pintype "input"))
      (node (ref "U1") (pin "24") (pinfunction "P0_0_24") (pintype "bidirectional"))
    )
    (net (code "52") (name "SW2") (class "Default")
      (node (ref "S1") (pin "T") (pinfunction "T_T") (pintype "input"))
      (node (ref "U1") (pin "4") (pinfunction "P0_1_4") (pintype "bidirectional"))
    )
    (net (code "53") (name "SW3") (class "Default")
      (node (ref "S1") (pin "2") (pinfunction "2_2") (pintype "input"))
      (node (ref "U1") (pin "25") (pinfunction "P0_2_25") (pintype "bidirectional"))
    )
    (net (code "54") (name "T1") (class "Default")
      (node (ref "R36") (pin "2") (pinfunction "2_2") (pintype "passive"))
      (node (ref "U10") (pin "18") (pinfunction "18_18") (pintype "passive"))
    )
    (net (code "55") (name "T2") (class "Default")
      (node (ref "R35") (pin "2") (pinfunction "2_2") (pintype "passive"))
      (node (ref "U10") (pin "17") (pinfunction "17_17") (pintype "passive"))
    )
    (net (code "56") (name "T3") (class "Default")
      (node (ref "R21") (pin "2") (pinfunction "2_2") (pintype "passive"))
      (node (ref "U10") (pin "16") (pinfunction "16_16") (pintype "passive"))
    )
    (net (code "57") (name "T4") (class "Default")
      (node (ref "R22") (pin "2") (pinfunction "2_2") (pintype "passive"))
      (node (ref "U10") (pin "15") (pinfunction "15_15") (pintype "passive"))
    )
    (net (code "58") (name "T5") (class "Default")
      (node (ref "R23") (pin "2") (pinfunction "2_2") (pintype "passive"))
      (node (ref "U10") (pin "14") (pinfunction "14_14") (pintype "passive"))
    )
    (net (code "59") (name "T6") (class "Default")
      (node (ref "R24") (pin "2") (pinfunction "2_2") (pintype "passive"))
      (node (ref "U10") (pin "13") (pinfunction "13_13") (pintype "passive"))
    )
    (net (code "60") (name "T7") (class "Default")
      (node (ref "R25") (pin "2") (pinfunction "2_2") (pintype "passive"))
      (node (ref "U10") (pin "12") (pinfunction "12_12") (pintype "passive"))
    )
    (net (code "61") (name "T8") (class "Default")
      (node (ref "R26") (pin "2") (pinfunction "2_2") (pintype "passive"))
      (node (ref "U10") (pin "11") (pinfunction "11_11") (pintype "passive"))
    )
    (net (code "62") (name "T9") (class "Default")
      (node (ref "R27") (pin "2") (pinfunction "2_2") (pintype "passive"))
      (node (ref "U10") (pin "10") (pinfunction "10_10") (pintype "passive"))
    )
    (net (code "63") (name "T10") (class "Default")
      (node (ref "R28") (pin "2") (pinfunction "2_2") (pintype "passive"))
      (node (ref "U10") (pin "9") (pinfunction "9_9") (pintype "passive"))
    )
    (net (code "64") (name "T11") (class "Default")
      (node (ref "R29") (pin "2") (pinfunction "2_2") (pintype "passive"))
      (node (ref "U10") (pin "8") (pinfunction "8_8") (pintype "passive"))
    )
    (net (code "65") (name "T12") (class "Default")
      (node (ref "R30") (pin "2") (pinfunction "2_2") (pintype "passive"))
      (node (ref "U10") (pin "7") (pinfunction "7_7") (pintype "passive"))
    )
    (net (code "66") (name "T13") (class "Default")
      (node (ref "R31") (pin "2") (pinfunction "2_2") (pintype "passive"))
      (node (ref "U10") (pin "6") (pinfunction "6_6") (pintype "passive"))
    )
    (net (code "67") (name "T14") (class "Default")
      (node (ref "R32") (pin "2") (pinfunction "2_2") (pintype "passive"))
      (node (ref "U10") (pin "5") (pinfunction "5_5") (pintype "passive"))
    )
    (net (code "68") (name "T15") (class "Default")
      (node (ref "R33") (pin "2") (pinfunction "2_2") (pintype "passive"))
      (node (ref "U10") (pin "4") (pinfunction "4_4") (pintype "passive"))
    )
    (net (code "69") (name "T16") (class "Default")
      (node (ref "R34") (pin "2") (pinfunction "2_2") (pintype "passive"))
      (node (ref "U10") (pin "3") (pinfunction "3_3") (pintype "passive"))
    )
    (net (code "70") (name "T17") (class "Default")
      (node (ref "R37") (pin "2") (pinfunction "2_2") (pintype "passive"))
      (node (ref "U10") (pin "2") (pinfunction "2_2") (pintype "passive"))
    )
    (net (code "71") (name "T18") (class "Default")
      (node (ref "R38") (pin "2") (pinfunction "2_2") (pintype "passive"))
      (node (ref "U10") (pin "1") (pinfunction "1_1") (pintype "passive"))
    )
    (net (code "72") (name "TRIG1") (class "Default")
      (node (ref "R36") (pin "1") (pinfunction "1_1") (pintype "passive"))
      (node (ref "U3") (pin "9") (pinfunction "CHAN0_9") (pintype "bidirectional"))
    )
    (net (code "73") (name "TRIG2") (class "Default")
      (node (ref "R35") (pin "1") (pinfunction "1_1") (pintype "passive"))
      (node (ref "U3") (pin "8") (pinfunction "CHAN1_8") (pintype "bidirectional"))
    )
    (net (code "74") (name "TRIG3") (class "Default")
      (node (ref "R21") (pin "1") (pinfunction "1_1") (pintype "passive"))
      (node (ref "U3") (pin "7") (pinfunction "CHAN2_7") (pintype "bidirectional"))
    )
    (net (code "75") (name "TRIG4") (class "Default")
      (node (ref "R22") (pin "1") (pinfunction "1_1") (pintype "passive"))
      (node (ref "U3") (pin "6") (pinfunction "CHAN3_6") (pintype "bidirectional"))
    )
    (net (code "76") (name "TRIG5") (class "Default")
      (node (ref "R23") (pin "1") (pinfunction "1_1") (pintype "passive"))
      (node (ref "U3") (pin "5") (pinfunction "CHAN4_5") (pintype "bidirectional"))
    )
    (net (code "77") (name "TRIG6") (class "Default")
      (node (ref "R24") (pin "1") (pinfunction "1_1") (pintype "passive"))
      (node (ref "U3") (pin "4") (pinfunction "CHAN5_4") (pintype "bidirectional"))
    )
    (net (code "78") (name "TRIG7") (class "Default")
      (node (ref "R25") (pin "1") (pinfunction "1_1") (pintype "passive"))
      (node (ref "U3") (pin "3") (pinfunction "CHAN6_3") (pintype "bidirectional"))
    )
    (net (code "79") (name "TRIG8") (class "Default")
      (node (ref "R26") (pin "1") (pinfunction "1_1") (pintype "passive"))
      (node (ref "U3") (pin "2") (pinfunction "CHAN7_2") (pintype "bidirectional"))
    )
    (net (code "80") (name "TRIG9") (class "Default")
      (node (ref "R27") (pin "1") (pinfunction "1_1") (pintype "passive"))
      (node (ref "U3") (pin "23") (pinfunction "CHAN8_23") (pintype "bidirectional"))
    )
    (net (code "81") (name "TRIG10") (class "Default")
      (node (ref "R28") (pin "1") (pinfunction "1_1") (pintype "passive"))
      (node (ref "U3") (pin "22") (pinfunction "CHAN9_22") (pintype "bidirectional"))
    )
    (net (code "82") (name "TRIG11") (class "Default")
      (node (ref "R29") (pin "1") (pinfunction "1_1") (pintype "passive"))
      (node (ref "U3") (pin "21") (pinfunction "CHAN10_21") (pintype "bidirectional"))
    )
    (net (code "83") (name "TRIG12") (class "Default")
      (node (ref "R30") (pin "1") (pinfunction "1_1") (pintype "passive"))
      (node (ref "U3") (pin "20") (pinfunction "CHAN11_20") (pintype "bidirectional"))
    )
    (net (code "84") (name "TRIG13") (class "Default")
      (node (ref "R31") (pin "1") (pinfunction "1_1") (pintype "passive"))
      (node (ref "U3") (pin "19") (pinfunction "CHAN12_19") (pintype "bidirectional"))
    )
    (net (code "85") (name "TRIG14") (class "Default")
      (node (ref "R32") (pin "1") (pinfunction "1_1") (pintype "passive"))
      (node (ref "U3") (pin "18") (pinfunction "CHAN13_18") (pintype "bidirectional"))
    )
    (net (code "86") (name "TRIG15") (class "Default")
      (node (ref "R33") (pin "1") (pinfunction "1_1") (pintype "passive"))
      (node (ref "U3") (pin "17") (pinfunction "CHAN14_17") (pintype "bidirectional"))
    )
    (net (code "87") (name "TRIG16") (class "Default")
      (node (ref "R34") (pin "1") (pinfunction "1_1") (pintype "passive"))
      (node (ref "U3") (pin "16") (pinfunction "CHAN15_16") (pintype "bidirectional"))
    )
    (net (code "88") (name "TRIG17") (class "Default")
      (node (ref "JP9") (pin "5") (pinfunction "5_5") (pintype "passive"))
      (node (ref "R37") (pin "1") (pinfunction "1_1") (pintype "passive"))
      (node (ref "U1") (pin "15") (pinfunction "P1_0_15") (pintype "bidirectional"))
    )
    (net (code "89") (name "TRIG18") (class "Default")
      (node (ref "JP9") (pin "4") (pinfunction "4_4") (pintype "passive"))
      (node (ref "R38") (pin "1") (pinfunction "1_1") (pintype "passive"))
      (node (ref "U1") (pin "13") (pinfunction "P1_1_13") (pintype "bidirectional"))
    )
    (net (code "90") (name "TX") (class "Default")
      (node (ref "JP3") (pin "2") (pinfunction "2_2") (pintype "passive"))
      (node (ref "U1") (pin "12") (pinfunction "P1_3_12") (pintype "bidirectional"))
    )
    (net (code "91") (name "USBVCC") (class "Default")
      (node (ref "JP3") (pin "4") (pinfunction "4_4") (pintype "passive"))
      (node (ref "S2") (pin "5") (pinfunction "5_5") (pintype "bidirectional"))
    )
    (net (code "92") (name "VBUS") (class "Default")
      (node (ref "F1") (pin "1") (pinfunction "1_1") (pintype "bidirectional"))
      (node (ref "JP5") (pin "2") (pinfunction "2_2") (pintype "passive"))
      (node (ref "JP9") (pin "1") (pinfunction "1_1") (pintype "passive"))
      (node (ref "S2") (pin "1") (pinfunction "1_1") (pintype "bidirectional"))
      (node (ref "SJ1") (pin "3") (pinfunction "3_3") (pintype "passive"))
    )
    (net (code "93") (name "XRES") (class "Default")
      (node (ref "JP9") (pin "3") (pinfunction "3_3") (pintype "passive"))
      (node (ref "U1") (pin "19") (pinfunction "XRES_19") (pintype "bidirectional"))
    )
    (net (code "94") (name "unconnected-(S2-Pad3)") (class "Default")
      (node (ref "S2") (pin "3") (pinfunction "3_3") (pintype "bidirectional"))
    )
    (net (code "95") (name "unconnected-(S2-Pad4)") (class "Default")
      (node (ref "S2") (pin "4") (pinfunction "4_4") (pintype "bidirectional"))
    )
    (net (code "96") (name "unconnected-(U1-SMP-Pad9)") (class "Default")
      (node (ref "U1") (pin "9") (pinfunction "SMP_9") (pintype "bidirectional"))
    )
    (net (code "97") (name "unconnected-(U2-NC-Pad1)") (class "Default")
      (node (ref "U2") (pin "1") (pinfunction "NC_1") (pintype "bidirectional"))
    )
    (net (code "98") (name "unconnected-(U2-RSV-Pad8)") (class "Default")
      (node (ref "U2") (pin "8") (pinfunction "RSV_8") (pintype "bidirectional"))
    )
    (net (code "99") (name "unconnected-(U4-OUT-Pad4)") (class "Default")
      (node (ref "U4") (pin "4") (pinfunction "OUT_4") (pintype "output"))
    )
    (net (code "100") (name "unconnected-(U5-BP-Pad4)") (class "Default")
      (node (ref "U5") (pin "4") (pinfunction "BP_4") (pintype "input"))
    )
    (net (code "101") (name "unconnected-(U7-GPIO2{slash}DCLK-Pad9)") (class "Default")
      (node (ref "U7") (pin "9") (pinfunction "GPIO2/DCLK_9") (pintype "bidirectional"))
    )
    (net (code "102") (name "unconnected-(U7-GPIO3{slash}SDATA-Pad10)") (class "Default")
      (node (ref "U7") (pin "10") (pinfunction "GPIO3/SDATA_10") (pintype "bidirectional"))
    )
    (net (code "103") (name "unconnected-(U7-GPIO4{slash}I2S_LROUT-Pad36)") (class "Default")
      (node (ref "U7") (pin "36") (pinfunction "GPIO4/I2S_LROUT_36") (pintype "bidirectional"))
    )
    (net (code "104") (name "unconnected-(U7-GPIO5{slash}I2C_MCLK-Pad25)") (class "Default")
      (node (ref "U7") (pin "25") (pinfunction "GPIO5/I2C_MCLK_25") (pintype "bidirectional"))
    )
    (net (code "105") (name "unconnected-(U7-GPIO6-Pad11)") (class "Default")
      (node (ref "U7") (pin "11") (pinfunction "GPIO6_11") (pintype "bidirectional"))
    )
    (net (code "106") (name "unconnected-(U7-GPIO7-Pad12)") (class "Default")
      (node (ref "U7") (pin "12") (pinfunction "GPIO7_12") (pintype "bidirectional"))
    )
    (net (code "107") (name "unconnected-(U7-LINEIN-Pad48)") (class "Default")
      (node (ref "U7") (pin "48") (pinfunction "LINEIN_48") (pintype "bidirectional"))
    )
    (net (code "108") (name "unconnected-(U7-RX-Pad26)") (class "Default")
      (node (ref "U7") (pin "26") (pinfunction "RX_26") (pintype "bidirectional"))
    )
    (net (code "109") (name "unconnected-(U7-TX-Pad27)") (class "Default")
      (node (ref "U7") (pin "27") (pinfunction "TX_27") (pintype "bidirectional"))
    )
    (net (code "110") (name "unconnected-(U7-VCO-Pad15)") (class "Default")
      (node (ref "U7") (pin "15") (pinfunction "VCO_15") (pintype "bidirectional"))
    )
  )
)
